# main.net
KiCad netlist of a schematic drawn in EAGLE
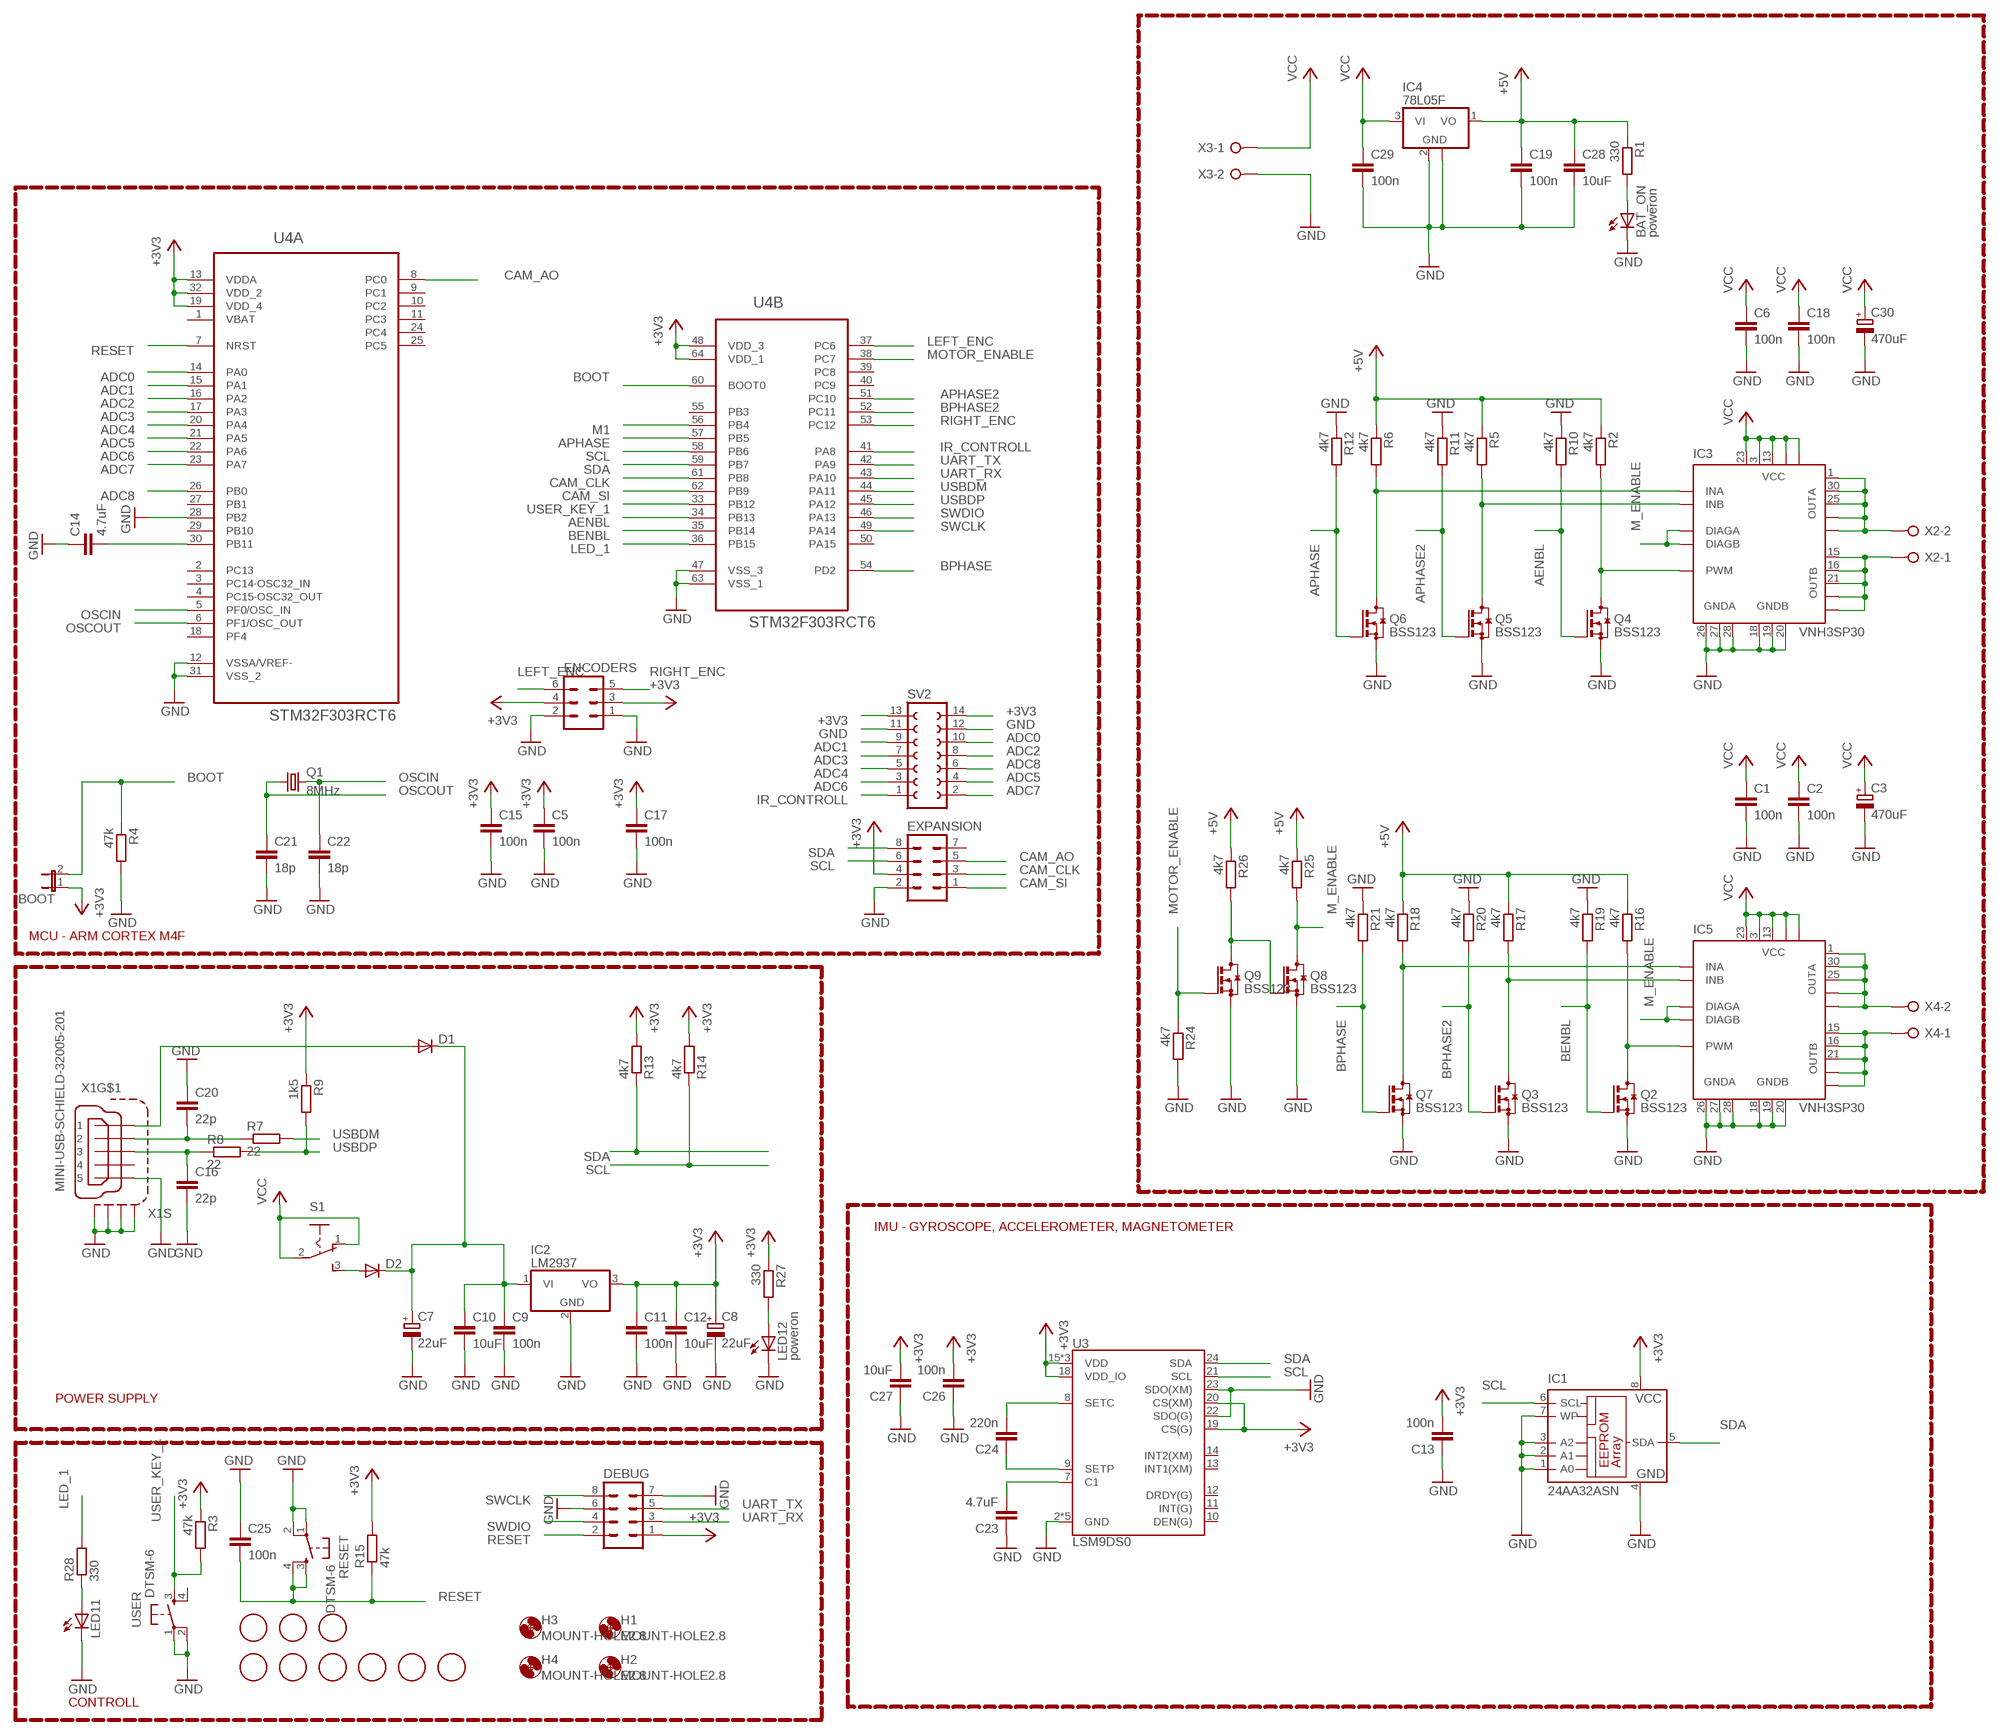
[diagram p0: schematic, sheet 1]

(export (version "E")
  (design (tool "Eeschema 10.0.6"))
  (components
    (comp (ref "BAT_ON")
      (value "poweron")
      (footprint "eagle-import:CHIPLED_1206")
      (libsource (lib "eagle-import") (part "LEDCHIPLED_1206"))
    )
    (comp (ref "BOOT")
      (value "JP1E")
      (footprint "eagle-import:JP1")
      (libsource (lib "eagle-import") (part "JP1E"))
    )
    (comp (ref "C1")
      (value "100n")
      (footprint "eagle-import:C0805")
      (libsource (lib "eagle-import") (part "C-EUC0805"))
    )
    (comp (ref "C2")
      (value "100n")
      (footprint "eagle-import:C0805")
      (libsource (lib "eagle-import") (part "C-EUC0805"))
    )
    (comp (ref "C3")
      (value "470uF")
      (footprint "eagle-import:140CLH-1014")
      (libsource (lib "eagle-import") (part "CPOL-EU140CLH-1014"))
    )
    (comp (ref "C5")
      (value "100n")
      (footprint "eagle-import:C0805")
      (libsource (lib "eagle-import") (part "C-EUC0805"))
    )
    (comp (ref "C6")
      (value "100n")
      (footprint "eagle-import:C0805")
      (libsource (lib "eagle-import") (part "C-EUC0805"))
    )
    (comp (ref "C7")
      (value "22uF")
      (footprint "eagle-import:153CLV-0505")
      (libsource (lib "eagle-import") (part "CPOL-EU153CLV-0505"))
    )
    (comp (ref "C8")
      (value "22uF")
      (footprint "eagle-import:153CLV-0505")
      (libsource (lib "eagle-import") (part "CPOL-EU153CLV-0505"))
    )
    (comp (ref "C9")
      (value "100n")
      (footprint "eagle-import:C0805")
      (libsource (lib "eagle-import") (part "C-EUC0805"))
    )
    (comp (ref "C10")
      (value "10uF")
      (footprint "eagle-import:C0805")
      (libsource (lib "eagle-import") (part "C-EUC0805"))
    )
    (comp (ref "C11")
      (value "100n")
      (footprint "eagle-import:C0805")
      (libsource (lib "eagle-import") (part "C-EUC0805"))
    )
    (comp (ref "C12")
      (value "10uF")
      (footprint "eagle-import:C0805")
      (libsource (lib "eagle-import") (part "C-EUC0805"))
    )
    (comp (ref "C13")
      (value "100n")
      (footprint "eagle-import:C0805")
      (libsource (lib "eagle-import") (part "C-EUC0805"))
    )
    (comp (ref "C14")
      (value "4.7uF")
      (footprint "eagle-import:C0805")
      (libsource (lib "eagle-import") (part "C-EUC0805"))
    )
    (comp (ref "C15")
      (value "100n")
      (footprint "eagle-import:C0805")
      (libsource (lib "eagle-import") (part "C-EUC0805"))
    )
    (comp (ref "C16")
      (value "22p")
      (footprint "eagle-import:C0805")
      (libsource (lib "eagle-import") (part "C-EUC0805"))
    )
    (comp (ref "C17")
      (value "100n")
      (footprint "eagle-import:C0805")
      (libsource (lib "eagle-import") (part "C-EUC0805"))
    )
    (comp (ref "C18")
      (value "100n")
      (footprint "eagle-import:C0805")
      (libsource (lib "eagle-import") (part "C-EUC0805"))
    )
    (comp (ref "C19")
      (value "100n")
      (footprint "eagle-import:C0805")
      (libsource (lib "eagle-import") (part "C-EUC0805"))
    )
    (comp (ref "C20")
      (value "22p")
      (footprint "eagle-import:C0805")
      (libsource (lib "eagle-import") (part "C-EUC0805"))
    )
    (comp (ref "C21")
      (value "18p")
      (footprint "eagle-import:C0805")
      (libsource (lib "eagle-import") (part "C-EUC0805"))
    )
    (comp (ref "C22")
      (value "18p")
      (footprint "eagle-import:C0805")
      (libsource (lib "eagle-import") (part "C-EUC0805"))
    )
    (comp (ref "C23")
      (value "4.7uF")
      (footprint "eagle-import:C0805")
      (libsource (lib "eagle-import") (part "C-EUC0805"))
    )
    (comp (ref "C24")
      (value "220n")
      (footprint "eagle-import:C0805")
      (libsource (lib "eagle-import") (part "C-EUC0805"))
    )
    (comp (ref "C25")
      (value "100n")
      (footprint "eagle-import:C0805")
      (libsource (lib "eagle-import") (part "C-EUC0805"))
    )
    (comp (ref "C26")
      (value "100n")
      (footprint "eagle-import:C0805")
      (libsource (lib "eagle-import") (part "C-EUC0805"))
    )
    (comp (ref "C27")
      (value "10uF")
      (footprint "eagle-import:C0805")
      (libsource (lib "eagle-import") (part "C-EUC0805"))
    )
    (comp (ref "C28")
      (value "10uF")
      (footprint "eagle-import:C0805")
      (libsource (lib "eagle-import") (part "C-EUC0805"))
    )
    (comp (ref "C29")
      (value "100n")
      (footprint "eagle-import:C0805")
      (libsource (lib "eagle-import") (part "C-EUC0805"))
    )
    (comp (ref "C30")
      (value "470uF")
      (footprint "eagle-import:140CLH-1014")
      (libsource (lib "eagle-import") (part "CPOL-EU140CLH-1014"))
    )
    (comp (ref "D1")
      (value "DIODE-SMB")
      (footprint "eagle-import:SMB")
      (libsource (lib "eagle-import") (part "DIODE-SMB"))
    )
    (comp (ref "D2")
      (value "DIODE-SMB")
      (footprint "eagle-import:SMB")
      (libsource (lib "eagle-import") (part "DIODE-SMB"))
    )
    (comp (ref "DEBUG")
      (value "MA04-2")
      (footprint "eagle-import:MA04-2")
      (libsource (lib "eagle-import") (part "MA04-2"))
    )
    (comp (ref "ENCODERS")
      (value "MA03-2")
      (footprint "eagle-import:MA03-2")
      (libsource (lib "eagle-import") (part "MA03-2"))
    )
    (comp (ref "EXPANSION")
      (value "MA04-2")
      (footprint "eagle-import:MA04-2")
      (libsource (lib "eagle-import") (part "MA04-2"))
    )
    (comp (ref "H1")
      (value "MOUNT-HOLE2.8")
      (footprint "eagle-import:2,8")
      (libsource (lib "eagle-import") (part "MOUNT-HOLE2.8"))
    )
    (comp (ref "H2")
      (value "MOUNT-HOLE2.8")
      (footprint "eagle-import:2,8")
      (libsource (lib "eagle-import") (part "MOUNT-HOLE2.8"))
    )
    (comp (ref "H3")
      (value "MOUNT-HOLE2.8")
      (footprint "eagle-import:2,8")
      (libsource (lib "eagle-import") (part "MOUNT-HOLE2.8"))
    )
    (comp (ref "H4")
      (value "MOUNT-HOLE2.8")
      (footprint "eagle-import:2,8")
      (libsource (lib "eagle-import") (part "MOUNT-HOLE2.8"))
    )
    (comp (ref "IC1")
      (value "24AA32ASN")
      (footprint "eagle-import:SO-08")
      (fields (field (name "MF") "MICROCHIP") (field (name "MPN") "24AA32A-I/SN"))
      (libsource (lib "eagle-import") (part "24SNAA32A"))
    )
    (comp (ref "IC2")
      (value "LM2937")
      (footprint "eagle-import:TO263-3")
      (libsource (lib "eagle-import") (part "LM2937"))
    )
    (comp (ref "IC3")
      (value "VNH3SP30")
      (footprint "eagle-import:MULTIPOWERSO-30")
      (fields (field (name "MPN") "VNH3SP30-E"))
      (libsource (lib "eagle-import") (part "VNH3SP30"))
    )
    (comp (ref "IC4")
      (value "78L05F")
      (footprint "eagle-import:SOT89")
      (libsource (lib "eagle-import") (part "78LF05"))
    )
    (comp (ref "IC5")
      (value "VNH3SP30")
      (footprint "eagle-import:MULTIPOWERSO-30")
      (fields (field (name "MPN") "VNH3SP30-E"))
      (libsource (lib "eagle-import") (part "VNH3SP30"))
    )
    (comp (ref "LED11")
      (value "LEDCHIPLED_1206")
      (footprint "eagle-import:CHIPLED_1206")
      (libsource (lib "eagle-import") (part "LEDCHIPLED_1206"))
    )
    (comp (ref "LED12")
      (value "poweron")
      (footprint "eagle-import:CHIPLED_1206")
      (libsource (lib "eagle-import") (part "LEDCHIPLED_1206"))
    )
    (comp (ref "Q1")
      (value "8MHz")
      (footprint "eagle-import:CTS406")
      (libsource (lib "eagle-import") (part "CRYSTALCTS406"))
    )
    (comp (ref "Q2")
      (value "BSS123")
      (footprint "eagle-import:SOT23")
      (libsource (lib "eagle-import") (part "BSS123"))
    )
    (comp (ref "Q3")
      (value "BSS123")
      (footprint "eagle-import:SOT23")
      (libsource (lib "eagle-import") (part "BSS123"))
    )
    (comp (ref "Q4")
      (value "BSS123")
      (footprint "eagle-import:SOT23")
      (libsource (lib "eagle-import") (part "BSS123"))
    )
    (comp (ref "Q5")
      (value "BSS123")
      (footprint "eagle-import:SOT23")
      (libsource (lib "eagle-import") (part "BSS123"))
    )
    (comp (ref "Q6")
      (value "BSS123")
      (footprint "eagle-import:SOT23")
      (libsource (lib "eagle-import") (part "BSS123"))
    )
    (comp (ref "Q7")
      (value "BSS123")
      (footprint "eagle-import:SOT23")
      (libsource (lib "eagle-import") (part "BSS123"))
    )
    (comp (ref "Q8")
      (value "BSS123")
      (footprint "eagle-import:SOT23")
      (libsource (lib "eagle-import") (part "BSS123"))
    )
    (comp (ref "Q9")
      (value "BSS123")
      (footprint "eagle-import:SOT23")
      (libsource (lib "eagle-import") (part "BSS123"))
    )
    (comp (ref "R1")
      (value "330")
      (footprint "eagle-import:M0805")
      (libsource (lib "eagle-import") (part "R-EU_M0805"))
    )
    (comp (ref "R2")
      (value "4k7")
      (footprint "eagle-import:M0805")
      (libsource (lib "eagle-import") (part "R-EU_M0805"))
    )
    (comp (ref "R3")
      (value "47k")
      (footprint "eagle-import:M0805")
      (libsource (lib "eagle-import") (part "R-EU_M0805"))
    )
    (comp (ref "R4")
      (value "47k")
      (footprint "eagle-import:M0805")
      (libsource (lib "eagle-import") (part "R-EU_M0805"))
    )
    (comp (ref "R5")
      (value "4k7")
      (footprint "eagle-import:M0805")
      (libsource (lib "eagle-import") (part "R-EU_M0805"))
    )
    (comp (ref "R6")
      (value "4k7")
      (footprint "eagle-import:M0805")
      (libsource (lib "eagle-import") (part "R-EU_M0805"))
    )
    (comp (ref "R7")
      (value "22")
      (footprint "eagle-import:M0805")
      (libsource (lib "eagle-import") (part "R-EU_M0805"))
    )
    (comp (ref "R8")
      (value "22")
      (footprint "eagle-import:M0805")
      (libsource (lib "eagle-import") (part "R-EU_M0805"))
    )
    (comp (ref "R9")
      (value "1k5")
      (footprint "eagle-import:M0805")
      (libsource (lib "eagle-import") (part "R-EU_M0805"))
    )
    (comp (ref "R10")
      (value "4k7")
      (footprint "eagle-import:M0805")
      (libsource (lib "eagle-import") (part "R-EU_M0805"))
    )
    (comp (ref "R11")
      (value "4k7")
      (footprint "eagle-import:M0805")
      (libsource (lib "eagle-import") (part "R-EU_M0805"))
    )
    (comp (ref "R12")
      (value "4k7")
      (footprint "eagle-import:M0805")
      (libsource (lib "eagle-import") (part "R-EU_M0805"))
    )
    (comp (ref "R13")
      (value "4k7")
      (footprint "eagle-import:M0805")
      (libsource (lib "eagle-import") (part "R-EU_M0805"))
    )
    (comp (ref "R14")
      (value "4k7")
      (footprint "eagle-import:M0805")
      (libsource (lib "eagle-import") (part "R-EU_M0805"))
    )
    (comp (ref "R15")
      (value "47k")
      (footprint "eagle-import:M0805")
      (libsource (lib "eagle-import") (part "R-EU_M0805"))
    )
    (comp (ref "R16")
      (value "4k7")
      (footprint "eagle-import:M0805")
      (libsource (lib "eagle-import") (part "R-EU_M0805"))
    )
    (comp (ref "R17")
      (value "4k7")
      (footprint "eagle-import:M0805")
      (libsource (lib "eagle-import") (part "R-EU_M0805"))
    )
    (comp (ref "R18")
      (value "4k7")
      (footprint "eagle-import:M0805")
      (libsource (lib "eagle-import") (part "R-EU_M0805"))
    )
    (comp (ref "R19")
      (value "4k7")
      (footprint "eagle-import:M0805")
      (libsource (lib "eagle-import") (part "R-EU_M0805"))
    )
    (comp (ref "R20")
      (value "4k7")
      (footprint "eagle-import:M0805")
      (libsource (lib "eagle-import") (part "R-EU_M0805"))
    )
    (comp (ref "R21")
      (value "4k7")
      (footprint "eagle-import:M0805")
      (libsource (lib "eagle-import") (part "R-EU_M0805"))
    )
    (comp (ref "R24")
      (value "4k7")
      (footprint "eagle-import:M0805")
      (libsource (lib "eagle-import") (part "R-EU_M0805"))
    )
    (comp (ref "R25")
      (value "4k7")
      (footprint "eagle-import:M0805")
      (libsource (lib "eagle-import") (part "R-EU_M0805"))
    )
    (comp (ref "R26")
      (value "4k7")
      (footprint "eagle-import:M0805")
      (libsource (lib "eagle-import") (part "R-EU_M0805"))
    )
    (comp (ref "R27")
      (value "330")
      (footprint "eagle-import:M0805")
      (libsource (lib "eagle-import") (part "R-EU_M0805"))
    )
    (comp (ref "R28")
      (value "330")
      (footprint "eagle-import:M0805")
      (libsource (lib "eagle-import") (part "R-EU_M0805"))
    )
    (comp (ref "RESET")
      (value "DTSM-6")
      (footprint "eagle-import:DTSM-6")
      (libsource (lib "eagle-import") (part "DTSM-6"))
    )
    (comp (ref "S1")
      (value "255SB")
      (footprint "eagle-import:255SB")
      (libsource (lib "eagle-import") (part "255SB"))
    )
    (comp (ref "SV2")
      (value "FE07-2")
      (footprint "eagle-import:FE07-2")
      (libsource (lib "eagle-import") (part "FE07-2"))
    )
    (comp (ref "U$1")
      (value "FIDUCIAL")
      (footprint "eagle-import:FIDUCIAL_1MM")
      (libsource (lib "eagle-import") (part "FIDUCIAL"))
    )
    (comp (ref "U$2")
      (value "FIDUCIAL")
      (footprint "eagle-import:FIDUCIAL_1MM")
      (libsource (lib "eagle-import") (part "FIDUCIAL"))
    )
    (comp (ref "U$3")
      (value "FIDUCIAL")
      (footprint "eagle-import:FIDUCIAL_1MM")
      (libsource (lib "eagle-import") (part "FIDUCIAL"))
    )
    (comp (ref "U$4")
      (value "FIDUCIAL")
      (footprint "eagle-import:FIDUCIAL_1MM")
      (libsource (lib "eagle-import") (part "FIDUCIAL"))
    )
    (comp (ref "U$5")
      (value "FIDUCIAL")
      (footprint "eagle-import:FIDUCIAL_1MM")
      (libsource (lib "eagle-import") (part "FIDUCIAL"))
    )
    (comp (ref "U$6")
      (value "FIDUCIAL")
      (footprint "eagle-import:FIDUCIAL_1MM")
      (libsource (lib "eagle-import") (part "FIDUCIAL"))
    )
    (comp (ref "U$7")
      (value "FIDUCIAL")
      (footprint "eagle-import:FIDUCIAL_1MM")
      (libsource (lib "eagle-import") (part "FIDUCIAL"))
    )
    (comp (ref "U$8")
      (value "FIDUCIAL")
      (footprint "eagle-import:FIDUCIAL_1MM")
      (libsource (lib "eagle-import") (part "FIDUCIAL"))
    )
    (comp (ref "U$9")
      (value "FIDUCIAL")
      (footprint "eagle-import:FIDUCIAL_1MM")
      (libsource (lib "eagle-import") (part "FIDUCIAL"))
    )
    (comp (ref "U3")
      (value "LSM9DS0")
      (footprint "eagle-import:LGA-24")
      (libsource (lib "eagle-import") (part "LSM9DS0"))
    )
    (comp (ref "U4")
      (value "STM32F303RCT6")
      (footprint "eagle-import:QFP50P1200X1200X160-64N")
      (libsource (lib "eagle-import") (part "STM32F303RCT6"))
    )
    (comp (ref "USER")
      (value "DTSM-6")
      (footprint "eagle-import:DTSM-6")
      (libsource (lib "eagle-import") (part "DTSM-6"))
    )
    (comp (ref "X1")
      (value "MINI-USB-SCHIELD-32005-201")
      (footprint "eagle-import:32005-201")
      (libsource (lib "eagle-import") (part "MINI-USB-SCHIELD-32005-201"))
    )
    (comp (ref "X2")
      (value "W237-02P")
      (footprint "eagle-import:W237-132")
      (libsource (lib "eagle-import") (part "W237-02P"))
    )
    (comp (ref "X3")
      (value "W237-02P")
      (footprint "eagle-import:W237-132")
      (libsource (lib "eagle-import") (part "W237-02P"))
    )
    (comp (ref "X4")
      (value "W237-02P")
      (footprint "eagle-import:W237-132")
      (libsource (lib "eagle-import") (part "W237-02P"))
    )
  )
  (nets
    (net (code "1") (name "+3V3") (class "Default")
      (node (ref "BOOT") (pin "1") (pinfunction "1_1") (pintype "passive"))
      (node (ref "C11") (pin "1") (pinfunction "1_1") (pintype "passive"))
      (node (ref "C12") (pin "1") (pinfunction "1_1") (pintype "passive"))
      (node (ref "C13") (pin "2") (pinfunction "2_2") (pintype "passive"))
      (node (ref "C15") (pin "1") (pinfunction "1_1") (pintype "passive"))
      (node (ref "C17") (pin "1") (pinfunction "1_1") (pintype "passive"))
      (node (ref "C26") (pin "2") (pinfunction "2_2") (pintype "passive"))
      (node (ref "C27") (pin "2") (pinfunction "2_2") (pintype "passive"))
      (node (ref "C5") (pin "1") (pinfunction "1_1") (pintype "passive"))
      (node (ref "C8") (pin "+") (pinfunction "+_+") (pintype "passive"))
      (node (ref "DEBUG") (pin "1") (pinfunction "1_1") (pintype "passive"))
      (node (ref "ENCODERS") (pin "3") (pinfunction "3_3") (pintype "passive"))
      (node (ref "ENCODERS") (pin "4") (pinfunction "4_4") (pintype "passive"))
      (node (ref "EXPANSION") (pin "4") (pinfunction "4_4") (pintype "passive"))
      (node (ref "IC1") (pin "8") (pinfunction "VCC_8") (pintype "power_in"))
      (node (ref "IC2") (pin "3") (pinfunction "VO_3") (pintype "passive"))
      (node (ref "R13") (pin "2") (pinfunction "2_2") (pintype "passive"))
      (node (ref "R14") (pin "2") (pinfunction "2_2") (pintype "passive"))
      (node (ref "R15") (pin "2") (pinfunction "2_2") (pintype "passive"))
      (node (ref "R27") (pin "1") (pinfunction "1_1") (pintype "passive"))
      (node (ref "R3") (pin "1") (pinfunction "1_1") (pintype "passive"))
      (node (ref "R9") (pin "1") (pinfunction "1_1") (pintype "passive"))
      (node (ref "SV2") (pin "13") (pinfunction "13_13") (pintype "passive"))
      (node (ref "SV2") (pin "14") (pinfunction "14_14") (pintype "passive"))
      (node (ref "U3") (pin "15") (pinfunction "VDD_15") (pintype "bidirectional"))
      (node (ref "U3") (pin "16") (pinfunction "VDD_16") (pintype "bidirectional"))
      (node (ref "U3") (pin "17") (pinfunction "VDD_17") (pintype "bidirectional"))
      (node (ref "U3") (pin "18") (pinfunction "VDD_IO_18") (pintype "bidirectional"))
      (node (ref "U3") (pin "19") (pinfunction "CS(G)_19") (pintype "bidirectional"))
      (node (ref "U3") (pin "20") (pinfunction "CS(XM)_20") (pintype "bidirectional"))
      (node (ref "U4") (pin "13") (pinfunction "VDDA_13") (pintype "power_in"))
      (node (ref "U4") (pin "19") (pinfunction "VDD_4_19") (pintype "power_in"))
      (node (ref "U4") (pin "32") (pinfunction "VDD_2_32") (pintype "power_in"))
      (node (ref "U4") (pin "48") (pinfunction "VDD_3_48") (pintype "power_in"))
      (node (ref "U4") (pin "64") (pinfunction "VDD_1_64") (pintype "power_in"))
    )
    (net (code "2") (name "+5V") (class "Default")
      (node (ref "C19") (pin "1") (pinfunction "1_1") (pintype "passive"))
      (node (ref "C28") (pin "1") (pinfunction "1_1") (pintype "passive"))
      (node (ref "IC4") (pin "1") (pinfunction "VO_1") (pintype "passive"))
      (node (ref "R1") (pin "1") (pinfunction "1_1") (pintype "passive"))
      (node (ref "R16") (pin "1") (pinfunction "1_1") (pintype "passive"))
      (node (ref "R17") (pin "1") (pinfunction "1_1") (pintype "passive"))
      (node (ref "R18") (pin "1") (pinfunction "1_1") (pintype "passive"))
      (node (ref "R2") (pin "1") (pinfunction "1_1") (pintype "passive"))
      (node (ref "R25") (pin "1") (pinfunction "1_1") (pintype "passive"))
      (node (ref "R26") (pin "1") (pinfunction "1_1") (pintype "passive"))
      (node (ref "R5") (pin "1") (pinfunction "1_1") (pintype "passive"))
      (node (ref "R6") (pin "1") (pinfunction "1_1") (pintype "passive"))
    )
    (net (code "3") (name "/ADC0") (class "Default")
      (node (ref "SV2") (pin "10") (pinfunction "10_10") (pintype "passive"))
      (node (ref "U4") (pin "14") (pinfunction "PA0_14") (pintype "bidirectional"))
    )
    (net (code "4") (name "/ADC1") (class "Default")
      (node (ref "SV2") (pin "9") (pinfunction "9_9") (pintype "passive"))
      (node (ref "U4") (pin "15") (pinfunction "PA1_15") (pintype "bidirectional"))
    )
    (net (code "5") (name "/ADC2") (class "Default")
      (node (ref "SV2") (pin "8") (pinfunction "8_8") (pintype "passive"))
      (node (ref "U4") (pin "16") (pinfunction "PA2_16") (pintype "bidirectional"))
    )
    (net (code "6") (name "/ADC3") (class "Default")
      (node (ref "SV2") (pin "7") (pinfunction "7_7") (pintype "passive"))
      (node (ref "U4") (pin "17") (pinfunction "PA3_17") (pintype "bidirectional"))
    )
    (net (code "7") (name "/ADC4") (class "Default")
      (node (ref "SV2") (pin "5") (pinfunction "5_5") (pintype "passive"))
      (node (ref "U4") (pin "20") (pinfunction "PA4_20") (pintype "bidirectional"))
    )
    (net (code "8") (name "/ADC5") (class "Default")
      (node (ref "SV2") (pin "4") (pinfunction "4_4") (pintype "passive"))
      (node (ref "U4") (pin "21") (pinfunction "PA5_21") (pintype "bidirectional"))
    )
    (net (code "9") (name "/ADC6") (class "Default")
      (node (ref "SV2") (pin "3") (pinfunction "3_3") (pintype "passive"))
      (node (ref "U4") (pin "22") (pinfunction "PA6_22") (pintype "bidirectional"))
    )
    (net (code "10") (name "/ADC7") (class "Default")
      (node (ref "SV2") (pin "2") (pinfunction "2_2") (pintype "passive"))
      (node (ref "U4") (pin "23") (pinfunction "PA7_23") (pintype "bidirectional"))
    )
    (net (code "11") (name "/ADC8") (class "Default")
      (node (ref "SV2") (pin "6") (pinfunction "6_6") (pintype "passive"))
      (node (ref "U4") (pin "26") (pinfunction "PB0_26") (pintype "bidirectional"))
    )
    (net (code "12") (name "/AENBL") (class "Default")
      (node (ref "Q4") (pin "1") (pinfunction "G_1") (pintype "passive"))
      (node (ref "R10") (pin "2") (pinfunction "2_2") (pintype "passive"))
      (node (ref "U4") (pin "34") (pinfunction "PB13_34") (pintype "bidirectional"))
    )
    (net (code "13") (name "/APHASE") (class "Default")
      (node (ref "Q6") (pin "1") (pinfunction "G_1") (pintype "passive"))
      (node (ref "R12") (pin "2") (pinfunction "2_2") (pintype "passive"))
      (node (ref "U4") (pin "57") (pinfunction "PB5_57") (pintype "bidirectional"))
    )
    (net (code "14") (name "/APHASE2") (class "Default")
      (node (ref "Q5") (pin "1") (pinfunction "G_1") (pintype "passive"))
      (node (ref "R11") (pin "2") (pinfunction "2_2") (pintype "passive"))
      (node (ref "U4") (pin "51") (pinfunction "PC10_51") (pintype "bidirectional"))
    )
    (net (code "15") (name "/BENBL") (class "Default")
      (node (ref "Q2") (pin "1") (pinfunction "G_1") (pintype "passive"))
      (node (ref "R19") (pin "2") (pinfunction "2_2") (pintype "passive"))
      (node (ref "U4") (pin "35") (pinfunction "PB14_35") (pintype "bidirectional"))
    )
    (net (code "16") (name "/BOOT") (class "Default")
      (node (ref "BOOT") (pin "2") (pinfunction "2_2") (pintype "passive"))
      (node (ref "R4") (pin "1") (pinfunction "1_1") (pintype "passive"))
      (node (ref "U4") (pin "60") (pinfunction "BOOT0_60") (pintype "input"))
    )
    (net (code "17") (name "/BPHASE") (class "Default")
      (node (ref "Q7") (pin "1") (pinfunction "G_1") (pintype "passive"))
      (node (ref "R21") (pin "2") (pinfunction "2_2") (pintype "passive"))
      (node (ref "U4") (pin "54") (pinfunction "PD2_54") (pintype "bidirectional"))
    )
    (net (code "18") (name "/BPHASE2") (class "Default")
      (node (ref "Q3") (pin "1") (pinfunction "G_1") (pintype "passive"))
      (node (ref "R20") (pin "2") (pinfunction "2_2") (pintype "passive"))
      (node (ref "U4") (pin "52") (pinfunction "PC11_52") (pintype "bidirectional"))
    )
    (net (code "19") (name "/CAM_AO") (class "Default")
      (node (ref "EXPANSION") (pin "5") (pinfunction "5_5") (pintype "passive"))
      (node (ref "U4") (pin "8") (pinfunction "PC0_8") (pintype "bidirectional"))
    )
    (net (code "20") (name "/CAM_CLK") (class "Default")
      (node (ref "EXPANSION") (pin "3") (pinfunction "3_3") (pintype "passive"))
      (node (ref "U4") (pin "61") (pinfunction "PB8_61") (pintype "bidirectional"))
    )
    (net (code "21") (name "/CAM_SI") (class "Default")
      (node (ref "EXPANSION") (pin "1") (pinfunction "1_1") (pintype "passive"))
      (node (ref "U4") (pin "62") (pinfunction "PB9_62") (pintype "bidirectional"))
    )
    (net (code "22") (name "/IR_CONTROLL") (class "Default")
      (node (ref "SV2") (pin "1") (pinfunction "1_1") (pintype "passive"))
      (node (ref "U4") (pin "41") (pinfunction "PA8_41") (pintype "bidirectional"))
    )
    (net (code "23") (name "/LED_1") (class "Default")
      (node (ref "R28") (pin "2") (pinfunction "2_2") (pintype "passive"))
      (node (ref "U4") (pin "36") (pinfunction "PB15_36") (pintype "bidirectional"))
    )
    (net (code "24") (name "/LEFT_ENC") (class "Default")
      (node (ref "ENCODERS") (pin "6") (pinfunction "6_6") (pintype "passive"))
      (node (ref "U4") (pin "37") (pinfunction "PC6_37") (pintype "bidirectional"))
    )
    (net (code "25") (name "/M1") (class "Default")
      (node (ref "U4") (pin "56") (pinfunction "PB4_56") (pintype "bidirectional"))
    )
    (net (code "26") (name "/MOTOR_ENABLE") (class "Default")
      (node (ref "Q9") (pin "1") (pinfunction "G_1") (pintype "passive"))
      (node (ref "R24") (pin "1") (pinfunction "1_1") (pintype "passive"))
      (node (ref "U4") (pin "38") (pinfunction "PC7_38") (pintype "bidirectional"))
    )
    (net (code "27") (name "/M_ENABLE") (class "Default")
      (node (ref "IC3") (pin "10") (pinfunction "DIAGB_10") (pintype "open_collector"))
      (node (ref "IC3") (pin "6") (pinfunction "DIAGA_6") (pintype "open_collector"))
      (node (ref "IC5") (pin "10") (pinfunction "DIAGB_10") (pintype "open_collector"))
      (node (ref "IC5") (pin "6") (pinfunction "DIAGA_6") (pintype "open_collector"))
      (node (ref "Q8") (pin "3") (pinfunction "D_3") (pintype "passive"))
      (node (ref "R25") (pin "2") (pinfunction "2_2") (pintype "passive"))
    )
    (net (code "28") (name "/OSCIN") (class "Default")
      (node (ref "C22") (pin "1") (pinfunction "1_1") (pintype "passive"))
      (node (ref "Q1") (pin "3") (pinfunction "2_3") (pintype "passive"))
      (node (ref "U4") (pin "5") (pinfunction "PF0/OSC_IN_5") (pintype "bidirectional"))
    )
    (net (code "29") (name "/OSCOUT") (class "Default")
      (node (ref "C21") (pin "1") (pinfunction "1_1") (pintype "passive"))
      (node (ref "Q1") (pin "1") (pinfunction "1_1") (pintype "passive"))
      (node (ref "U4") (pin "6") (pinfunction "PF1/OSC_OUT_6") (pintype "bidirectional"))
    )
    (net (code "30") (name "/RESET") (class "Default")
      (node (ref "C25") (pin "2") (pinfunction "2_2") (pintype "passive"))
      (node (ref "DEBUG") (pin "2") (pinfunction "2_2") (pintype "passive"))
      (node (ref "R15") (pin "1") (pinfunction "1_1") (pintype "passive"))
      (node (ref "RESET") (pin "3") (pinfunction "3_3") (pintype "passive"))
      (node (ref "RESET") (pin "4") (pinfunction "4_4") (pintype "passive"))
      (node (ref "U4") (pin "7") (pinfunction "NRST_7") (pintype "bidirectional"))
    )
    (net (code "31") (name "/RIGHT_ENC") (class "Default")
      (node (ref "ENCODERS") (pin "5") (pinfunction "5_5") (pintype "passive"))
      (node (ref "U4") (pin "53") (pinfunction "PC12_53") (pintype "bidirectional"))
    )
    (net (code "32") (name "/SCL") (class "Default")
      (node (ref "EXPANSION") (pin "6") (pinfunction "6_6") (pintype "passive"))
      (node (ref "IC1") (pin "6") (pinfunction "SCL_6") (pintype "input"))
      (node (ref "R14") (pin "1") (pinfunction "1_1") (pintype "passive"))
      (node (ref "U3") (pin "21") (pinfunction "SCL_21") (pintype "bidirectional"))
      (node (ref "U4") (pin "58") (pinfunction "PB6_58") (pintype "bidirectional"))
    )
    (net (code "33") (name "/SDA") (class "Default")
      (node (ref "EXPANSION") (pin "8") (pinfunction "8_8") (pintype "passive"))
      (node (ref "IC1") (pin "5") (pinfunction "SDA_5") (pintype "bidirectional"))
      (node (ref "R13") (pin "1") (pinfunction "1_1") (pintype "passive"))
      (node (ref "U3") (pin "24") (pinfunction "SDA_24") (pintype "bidirectional"))
      (node (ref "U4") (pin "59") (pinfunction "PB7_59") (pintype "bidirectional"))
    )
    (net (code "34") (name "/SWCLK") (class "Default")
      (node (ref "DEBUG") (pin "8") (pinfunction "8_8") (pintype "passive"))
      (node (ref "U4") (pin "49") (pinfunction "PA14_49") (pintype "bidirectional"))
    )
    (net (code "35") (name "/SWDIO") (class "Default")
      (node (ref "DEBUG") (pin "4") (pinfunction "4_4") (pintype "passive"))
      (node (ref "U4") (pin "46") (pinfunction "PA13_46") (pintype "bidirectional"))
    )
    (net (code "36") (name "/UART_RX") (class "Default")
      (node (ref "DEBUG") (pin "3") (pinfunction "3_3") (pintype "passive"))
      (node (ref "U4") (pin "43") (pinfunction "PA10_43") (pintype "bidirectional"))
    )
    (net (code "37") (name "/UART_TX") (class "Default")
      (node (ref "DEBUG") (pin "5") (pinfunction "5_5") (pintype "passive"))
      (node (ref "U4") (pin "42") (pinfunction "PA9_42") (pintype "bidirectional"))
    )
    (net (code "38") (name "/USBDM") (class "Default")
      (node (ref "R7") (pin "2") (pinfunction "2_2") (pintype "passive"))
      (node (ref "U4") (pin "44") (pinfunction "PA11_44") (pintype "bidirectional"))
    )
    (net (code "39") (name "/USBDP") (class "Default")
      (node (ref "R8") (pin "2") (pinfunction "2_2") (pintype "passive"))
      (node (ref "R9") (pin "2") (pinfunction "2_2") (pintype "passive"))
      (node (ref "U4") (pin "45") (pinfunction "PA12_45") (pintype "bidirectional"))
    )
    (net (code "40") (name "/USER_KEY_1") (class "Default")
      (node (ref "R3") (pin "2") (pinfunction "2_2") (pintype "passive"))
      (node (ref "U4") (pin "33") (pinfunction "PB12_33") (pintype "bidirectional"))
      (node (ref "USER") (pin "3") (pinfunction "3_3") (pintype "passive"))
    )
    (net (code "41") (name "/VBAT") (class "Default")
      (node (ref "U4") (pin "1") (pinfunction "VBAT_1") (pintype "power_in"))
    )
    (net (code "42") (name "GND") (class "Default")
      (node (ref "BAT_ON") (pin "C") (pinfunction "C_C") (pintype "passive"))
      (node (ref "C1") (pin "2") (pinfunction "2_2") (pintype "passive"))
      (node (ref "C10") (pin "2") (pinfunction "2_2") (pintype "passive"))
      (node (ref "C11") (pin "2") (pinfunction "2_2") (pintype "passive"))
      (node (ref "C12") (pin "2") (pinfunction "2_2") (pintype "passive"))
      (node (ref "C13") (pin "1") (pinfunction "1_1") (pintype "passive"))
      (node (ref "C14") (pin "1") (pinfunction "1_1") (pintype "passive"))
      (node (ref "C15") (pin "2") (pinfunction "2_2") (pintype "passive"))
      (node (ref "C16") (pin "2") (pinfunction "2_2") (pintype "passive"))
      (node (ref "C17") (pin "2") (pinfunction "2_2") (pintype "passive"))
      (node (ref "C18") (pin "2") (pinfunction "2_2") (pintype "passive"))
      (node (ref "C19") (pin "2") (pinfunction "2_2") (pintype "passive"))
      (node (ref "C2") (pin "2") (pinfunction "2_2") (pintype "passive"))
      (node (ref "C20") (pin "1") (pinfunction "1_1") (pintype "passive"))
      (node (ref "C21") (pin "2") (pinfunction "2_2") (pintype "passive"))
      (node (ref "C22") (pin "2") (pinfunction "2_2") (pintype "passive"))
      (node (ref "C23") (pin "1") (pinfunction "1_1") (pintype "passive"))
      (node (ref "C25") (pin "1") (pinfunction "1_1") (pintype "passive"))
      (node (ref "C26") (pin "1") (pinfunction "1_1") (pintype "passive"))
      (node (ref "C27") (pin "1") (pinfunction "1_1") (pintype "passive"))
      (node (ref "C28") (pin "2") (pinfunction "2_2") (pintype "passive"))
      (node (ref "C29") (pin "2") (pinfunction "2_2") (pintype "passive"))
      (node (ref "C3") (pin "-") (pinfunction "-_-") (pintype "passive"))
      (node (ref "C30") (pin "-") (pinfunction "-_-") (pintype "passive"))
      (node (ref "C5") (pin "2") (pinfunction "2_2") (pintype "passive"))
      (node (ref "C6") (pin "2") (pinfunction "2_2") (pintype "passive"))
      (node (ref "C7") (pin "-") (pinfunction "-_-") (pintype "passive"))
      (node (ref "C8") (pin "-") (pinfunction "-_-") (pintype "passive"))
      (node (ref "C9") (pin "2") (pinfunction "2_2") (pintype "passive"))
      (node (ref "DEBUG") (pin "6") (pinfunction "6_6") (pintype "passive"))
      (node (ref "DEBUG") (pin "7") (pinfunction "7_7") (pintype "passive"))
      (node (ref "ENCODERS") (pin "1") (pinfunction "1_1") (pintype "passive"))
      (node (ref "ENCODERS") (pin "2") (pinfunction "2_2") (pintype "passive"))
      (node (ref "EXPANSION") (pin "2") (pinfunction "2_2") (pintype "passive"))
      (node (ref "IC1") (pin "1") (pinfunction "A0_1") (pintype "input"))
      (node (ref "IC1") (pin "2") (pinfunction "A1_2") (pintype "input"))
      (node (ref "IC1") (pin "3") (pinfunction "A2_3") (pintype "input"))
      (node (ref "IC1") (pin "4") (pinfunction "GND_4") (pintype "power_in"))
      (node (ref "IC1") (pin "7") (pinfunction "WP_7") (pintype "input"))
      (node (ref "IC2") (pin "2") (pinfunction "GND_2") (pintype "passive"))
      (node (ref "IC3") (pin "18") (pinfunction "GNDB_18") (pintype "power_in"))
      (node (ref "IC3") (pin "19") (pinfunction "GNDB_19") (pintype "power_in"))
      (node (ref "IC3") (pin "20") (pinfunction "GNDB_20") (pintype "power_in"))
      (node (ref "IC3") (pin "26") (pinfunction "GNDA_26") (pintype "power_in"))
      (node (ref "IC3") (pin "27") (pinfunction "GNDA_27") (pintype "power_in"))
      (node (ref "IC3") (pin "28") (pinfunction "GNDA_28") (pintype "power_in"))
      (node (ref "IC4") (pin "2") (pinfunction "GND_2") (pintype "passive"))
      (node (ref "IC4") (pin "2@1") (pinfunction "GND_2@1") (pintype "passive"))
      (node (ref "IC5") (pin "18") (pinfunction "GNDB_18") (pintype "power_in"))
      (node (ref "IC5") (pin "19") (pinfunction "GNDB_19") (pintype "power_in"))
      (node (ref "IC5") (pin "20") (pinfunction "GNDB_20") (pintype "power_in"))
      (node (ref "IC5") (pin "26") (pinfunction "GNDA_26") (pintype "power_in"))
      (node (ref "IC5") (pin "27") (pinfunction "GNDA_27") (pintype "power_in"))
      (node (ref "IC5") (pin "28") (pinfunction "GNDA_28") (pintype "power_in"))
      (node (ref "LED11") (pin "C") (pinfunction "C_C") (pintype "passive"))
      (node (ref "LED12") (pin "C") (pinfunction "C_C") (pintype "passive"))
      (node (ref "Q2") (pin "2") (pinfunction "S_2") (pintype "passive"))
      (node (ref "Q3") (pin "2") (pinfunction "S_2") (pintype "passive"))
      (node (ref "Q4") (pin "2") (pinfunction "S_2") (pintype "passive"))
      (node (ref "Q5") (pin "2") (pinfunction "S_2") (pintype "passive"))
      (node (ref "Q6") (pin "2") (pinfunction "S_2") (pintype "passive"))
      (node (ref "Q7") (pin "2") (pinfunction "S_2") (pintype "passive"))
      (node (ref "Q8") (pin "2") (pinfunction "S_2") (pintype "passive"))
      (node (ref "Q9") (pin "2") (pinfunction "S_2") (pintype "passive"))
      (node (ref "R10") (pin "1") (pinfunction "1_1") (pintype "passive"))
      (node (ref "R11") (pin "1") (pinfunction "1_1") (pintype "passive"))
      (node (ref "R12") (pin "1") (pinfunction "1_1") (pintype "passive"))
      (node (ref "R19") (pin "1") (pinfunction "1_1") (pintype "passive"))
      (node (ref "R20") (pin "1") (pinfunction "1_1") (pintype "passive"))
      (node (ref "R21") (pin "1") (pinfunction "1_1") (pintype "passive"))
      (node (ref "R24") (pin "2") (pinfunction "2_2") (pintype "passive"))
      (node (ref "R4") (pin "2") (pinfunction "2_2") (pintype "passive"))
      (node (ref "RESET") (pin "1") (pinfunction "1_1") (pintype "passive"))
      (node (ref "RESET") (pin "2") (pinfunction "2_2") (pintype "passive"))
      (node (ref "SV2") (pin "11") (pinfunction "11_11") (pintype "passive"))
      (node (ref "SV2") (pin "12") (pinfunction "12_12") (pintype "passive"))
      (node (ref "U3") (pin "2") (pinfunction "GND_2") (pintype "bidirectional"))
      (node (ref "U3") (pin "22") (pinfunction "SDO(G)_22") (pintype "bidirectional"))
      (node (ref "U3") (pin "23") (pinfunction "SDO(XM)_23") (pintype "bidirectional"))
      (node (ref "U3") (pin "3") (pinfunction "GND_3") (pintype "bidirectional"))
      (node (ref "U3") (pin "4") (pinfunction "GND_4") (pintype "bidirectional"))
      (node (ref "U3") (pin "5") (pinfunction "GND_5") (pintype "bidirectional"))
      (node (ref "U3") (pin "6") (pinfunction "GND_6") (pintype "bidirectional"))
      (node (ref "U4") (pin "12") (pinfunction "VSSA/VREF-_12") (pintype "power_in"))
      (node (ref "U4") (pin "28") (pinfunction "PB2_28") (pintype "bidirectional"))
      (node (ref "U4") (pin "31") (pinfunction "VSS_2_31") (pintype "passive"))
      (node (ref "U4") (pin "47") (pinfunction "VSS_3_47") (pintype "passive"))
      (node (ref "U4") (pin "63") (pinfunction "VSS_1_63") (pintype "passive"))
      (node (ref "USER") (pin "1") (pinfunction "1_1") (pintype "passive"))
      (node (ref "USER") (pin "2") (pinfunction "2_2") (pintype "passive"))
      (node (ref "X1") (pin "5") (pinfunction "5_5") (pintype "passive"))
      (node (ref "X1") (pin "M1") (pinfunction "S1_M1") (pintype "passive"))
      (node (ref "X1") (pin "M2") (pinfunction "S2_M2") (pintype "passive"))
      (node (ref "X1") (pin "M3") (pinfunction "S3_M3") (pintype "passive"))
      (node (ref "X1") (pin "M4") (pinfunction "S4_M4") (pintype "passive"))
      (node (ref "X3") (pin "2") (pinfunction "KL_2") (pintype "passive"))
    )
    (net (code "43") (name "Net-(BAT_ON-PadA)") (class "Default")
      (node (ref "BAT_ON") (pin "A") (pinfunction "A_A") (pintype "passive"))
      (node (ref "R1") (pin "2") (pinfunction "2_2") (pintype "passive"))
    )
    (net (code "44") (name "Net-(C16-Pad1)") (class "Default")
      (node (ref "C16") (pin "1") (pinfunction "1_1") (pintype "passive"))
      (node (ref "R8") (pin "1") (pinfunction "1_1") (pintype "passive"))
      (node (ref "X1") (pin "3") (pinfunction "3_3") (pintype "passive"))
    )
    (net (code "45") (name "Net-(C20-Pad2)") (class "Default")
      (node (ref "C20") (pin "2") (pinfunction "2_2") (pintype "passive"))
      (node (ref "R7") (pin "1") (pinfunction "1_1") (pintype "passive"))
      (node (ref "X1") (pin "2") (pinfunction "2_2") (pintype "passive"))
    )
    (net (code "46") (name "Net-(D1-PadA)") (class "Default")
      (node (ref "D1") (pin "A") (pinfunction "A_A") (pintype "passive"))
      (node (ref "X1") (pin "1") (pinfunction "1_1") (pintype "passive"))
    )
    (net (code "47") (name "Net-(IC2-VI)") (class "Default")
      (node (ref "C10") (pin "1") (pinfunction "1_1") (pintype "passive"))
      (node (ref "C7") (pin "+") (pinfunction "+_+") (pintype "passive"))
      (node (ref "C9") (pin "1") (pinfunction "1_1") (pintype "passive"))
      (node (ref "D1") (pin "C") (pinfunction "C_C") (pintype "passive"))
      (node (ref "D2") (pin "C") (pinfunction "C_C") (pintype "passive"))
      (node (ref "IC2") (pin "1") (pinfunction "VI_1") (pintype "input"))
    )
    (net (code "48") (name "Net-(IC3-INA)") (class "Default")
      (node (ref "IC3") (pin "5") (pinfunction "INA_5") (pintype "input"))
      (node (ref "Q6") (pin "3") (pinfunction "D_3") (pintype "passive"))
      (node (ref "R6") (pin "2") (pinfunction "2_2") (pintype "passive"))
    )
    (net (code "49") (name "Net-(IC3-INB)") (class "Default")
      (node (ref "IC3") (pin "11") (pinfunction "INB_11") (pintype "input"))
      (node (ref "Q5") (pin "3") (pinfunction "D_3") (pintype "passive"))
      (node (ref "R5") (pin "2") (pinfunction "2_2") (pintype "passive"))
    )
    (net (code "50") (name "Net-(IC3-PWM)") (class "Default")
      (node (ref "IC3") (pin "8") (pinfunction "PWM_8") (pintype "input"))
      (node (ref "Q4") (pin "3") (pinfunction "D_3") (pintype "passive"))
      (node (ref "R2") (pin "2") (pinfunction "2_2") (pintype "passive"))
    )
    (net (code "51") (name "Net-(IC5-INA)") (class "Default")
      (node (ref "IC5") (pin "5") (pinfunction "INA_5") (pintype "input"))
      (node (ref "Q7") (pin "3") (pinfunction "D_3") (pintype "passive"))
      (node (ref "R18") (pin "2") (pinfunction "2_2") (pintype "passive"))
    )
    (net (code "52") (name "Net-(IC5-INB)") (class "Default")
      (node (ref "IC5") (pin "11") (pinfunction "INB_11") (pintype "input"))
      (node (ref "Q3") (pin "3") (pinfunction "D_3") (pintype "passive"))
      (node (ref "R17") (pin "2") (pinfunction "2_2") (pintype "passive"))
    )
    (net (code "53") (name "Net-(IC5-PWM)") (class "Default")
      (node (ref "IC5") (pin "8") (pinfunction "PWM_8") (pintype "input"))
      (node (ref "Q2") (pin "3") (pinfunction "D_3") (pintype "passive"))
      (node (ref "R16") (pin "2") (pinfunction "2_2") (pintype "passive"))
    )
    (net (code "54") (name "Net-(LED11-PadA)") (class "Default")
      (node (ref "LED11") (pin "A") (pinfunction "A_A") (pintype "passive"))
      (node (ref "R28") (pin "1") (pinfunction "1_1") (pintype "passive"))
    )
    (net (code "55") (name "Net-(LED12-PadA)") (class "Default")
      (node (ref "LED12") (pin "A") (pinfunction "A_A") (pintype "passive"))
      (node (ref "R27") (pin "2") (pinfunction "2_2") (pintype "passive"))
    )
    (net (code "56") (name "Net-(Q8-G)") (class "Default")
      (node (ref "Q8") (pin "1") (pinfunction "G_1") (pintype "passive"))
      (node (ref "Q9") (pin "3") (pinfunction "D_3") (pintype "passive"))
      (node (ref "R26") (pin "2") (pinfunction "2_2") (pintype "passive"))
    )
    (net (code "57") (name "Net-(S1-S)") (class "Default")
      (node (ref "D2") (pin "A") (pinfunction "A_A") (pintype "passive"))
      (node (ref "S1") (pin "3") (pinfunction "S_3") (pintype "passive"))
    )
    (net (code "58") (name "Net-(U3-C1)") (class "Default")
      (node (ref "C23") (pin "2") (pinfunction "2_2") (pintype "passive"))
      (node (ref "U3") (pin "7") (pinfunction "C1_7") (pintype "bidirectional"))
    )
    (net (code "59") (name "Net-(U3-SETC)") (class "Default")
      (node (ref "C24") (pin "2") (pinfunction "2_2") (pintype "passive"))
      (node (ref "U3") (pin "8") (pinfunction "SETC_8") (pintype "bidirectional"))
    )
    (net (code "60") (name "Net-(U3-SETP)") (class "Default")
      (node (ref "C24") (pin "1") (pinfunction "1_1") (pintype "passive"))
      (node (ref "U3") (pin "9") (pinfunction "SETP_9") (pintype "bidirectional"))
    )
    (net (code "61") (name "Net-(U4A-PB11)") (class "Default")
      (node (ref "C14") (pin "2") (pinfunction "2_2") (pintype "passive"))
      (node (ref "U4") (pin "30") (pinfunction "PB11_30") (pintype "bidirectional"))
    )
    (net (code "62") (name "Net-(X2A-KL)") (class "Default")
      (node (ref "IC3") (pin "15") (pinfunction "OUTB_15") (pintype "output"))
      (node (ref "IC3") (pin "16") (pinfunction "OUTB_16") (pintype "passive"))
      (node (ref "IC3") (pin "21") (pinfunction "OUTB_21") (pintype "passive"))
      (node (ref "IC3") (pin "OUTB") (pinfunction "OUTB_OUTB") (pintype "passive"))
      (node (ref "IC3") (pin "OUTB@1") (pinfunction "OUTB_OUTB@1") (pintype "passive"))
      (node (ref "X2") (pin "1") (pinfunction "KL_1") (pintype "passive"))
    )
    (net (code "63") (name "Net-(X2B-KL)") (class "Default")
      (node (ref "IC3") (pin "1") (pinfunction "OUTA_1") (pintype "output"))
      (node (ref "IC3") (pin "25") (pinfunction "OUTA_25") (pintype "passive"))
      (node (ref "IC3") (pin "30") (pinfunction "OUTA_30") (pintype "passive"))
      (node (ref "IC3") (pin "OUTA") (pinfunction "OUTA_OUTA") (pintype "passive"))
      (node (ref "IC3") (pin "OUTA@1") (pinfunction "OUTA_OUTA@1") (pintype "passive"))
      (node (ref "X2") (pin "2") (pinfunction "KL_2") (pintype "passive"))
    )
    (net (code "64") (name "Net-(X4A-KL)") (class "Default")
      (node (ref "IC5") (pin "15") (pinfunction "OUTB_15") (pintype "output"))
      (node (ref "IC5") (pin "16") (pinfunction "OUTB_16") (pintype "passive"))
      (node (ref "IC5") (pin "21") (pinfunction "OUTB_21") (pintype "passive"))
      (node (ref "IC5") (pin "OUTB") (pinfunction "OUTB_OUTB") (pintype "passive"))
      (node (ref "IC5") (pin "OUTB@1") (pinfunction "OUTB_OUTB@1") (pintype "passive"))
      (node (ref "X4") (pin "1") (pinfunction "KL_1") (pintype "passive"))
    )
    (net (code "65") (name "Net-(X4B-KL)") (class "Default")
      (node (ref "IC5") (pin "1") (pinfunction "OUTA_1") (pintype "output"))
      (node (ref "IC5") (pin "25") (pinfunction "OUTA_25") (pintype "passive"))
      (node (ref "IC5") (pin "30") (pinfunction "OUTA_30") (pintype "passive"))
      (node (ref "IC5") (pin "OUTA") (pinfunction "OUTA_OUTA") (pintype "passive"))
      (node (ref "IC5") (pin "OUTA@1") (pinfunction "OUTA_OUTA@1") (pintype "passive"))
      (node (ref "X4") (pin "2") (pinfunction "KL_2") (pintype "passive"))
    )
    (net (code "66") (name "VCC") (class "Default")
      (node (ref "C1") (pin "1") (pinfunction "1_1") (pintype "passive"))
      (node (ref "C18") (pin "1") (pinfunction "1_1") (pintype "passive"))
      (node (ref "C2") (pin "1") (pinfunction "1_1") (pintype "passive"))
      (node (ref "C29") (pin "1") (pinfunction "1_1") (pintype "passive"))
      (node (ref "C3") (pin "+") (pinfunction "+_+") (pintype "passive"))
      (node (ref "C30") (pin "+") (pinfunction "+_+") (pintype "passive"))
      (node (ref "C6") (pin "1") (pinfunction "1_1") (pintype "passive"))
      (node (ref "IC3") (pin "13") (pinfunction "VCC_13") (pintype "power_in"))
      (node (ref "IC3") (pin "23") (pinfunction "VCC_23") (pintype "power_in"))
      (node (ref "IC3") (pin "3") (pinfunction "VCC_3") (pintype "power_in"))
      (node (ref "IC3") (pin "VCC") (pinfunction "VCC_VCC") (pintype "power_in"))
      (node (ref "IC3") (pin "VCC@1") (pinfunction "VCC_VCC@1") (pintype "power_in"))
      (node (ref "IC4") (pin "3") (pinfunction "VI_3") (pintype "input"))
      (node (ref "IC5") (pin "13") (pinfunction "VCC_13") (pintype "power_in"))
      (node (ref "IC5") (pin "23") (pinfunction "VCC_23") (pintype "power_in"))
      (node (ref "IC5") (pin "3") (pinfunction "VCC_3") (pintype "power_in"))
      (node (ref "IC5") (pin "VCC") (pinfunction "VCC_VCC") (pintype "power_in"))
      (node (ref "IC5") (pin "VCC@1") (pinfunction "VCC_VCC@1") (pintype "power_in"))
      (node (ref "S1") (pin "1") (pinfunction "O_1") (pintype "passive"))
      (node (ref "S1") (pin "2") (pinfunction "P_2") (pintype "passive"))
      (node (ref "X3") (pin "1") (pinfunction "KL_1") (pintype "passive"))
    )
    (net (code "67") (name "unconnected-(EXPANSION-Pad7)") (class "Default")
      (node (ref "EXPANSION") (pin "7") (pinfunction "7_7") (pintype "passive"))
    )
    (net (code "68") (name "unconnected-(U3-DEN(G)-Pad10)") (class "Default")
      (node (ref "U3") (pin "10") (pinfunction "DEN(G)_10") (pintype "bidirectional"))
    )
    (net (code "69") (name "unconnected-(U3-DRDY(G)-Pad12)") (class "Default")
      (node (ref "U3") (pin "12") (pinfunction "DRDY(G)_12") (pintype "bidirectional"))
    )
    (net (code "70") (name "unconnected-(U3-INT(G)-Pad11)") (class "Default")
      (node (ref "U3") (pin "11") (pinfunction "INT(G)_11") (pintype "bidirectional"))
    )
    (net (code "71") (name "unconnected-(U3-INT1(XM)-Pad13)") (class "Default")
      (node (ref "U3") (pin "13") (pinfunction "INT1(XM)_13") (pintype "bidirectional"))
    )
    (net (code "72") (name "unconnected-(U3-INT2(XM)-Pad14)") (class "Default")
      (node (ref "U3") (pin "14") (pinfunction "INT2(XM)_14") (pintype "bidirectional"))
    )
    (net (code "73") (name "unconnected-(U4A-PB1-Pad27)") (class "Default")
      (node (ref "U4") (pin "27") (pinfunction "PB1_27") (pintype "bidirectional"))
    )
    (net (code "74") (name "unconnected-(U4A-PB10-Pad29)") (class "Default")
      (node (ref "U4") (pin "29") (pinfunction "PB10_29") (pintype "bidirectional"))
    )
    (net (code "75") (name "unconnected-(U4A-PC1-Pad9)") (class "Default")
      (node (ref "U4") (pin "9") (pinfunction "PC1_9") (pintype "bidirectional"))
    )
    (net (code "76") (name "unconnected-(U4A-PC2-Pad10)") (class "Default")
      (node (ref "U4") (pin "10") (pinfunction "PC2_10") (pintype "bidirectional"))
    )
    (net (code "77") (name "unconnected-(U4A-PC3-Pad11)") (class "Default")
      (node (ref "U4") (pin "11") (pinfunction "PC3_11") (pintype "bidirectional"))
    )
    (net (code "78") (name "unconnected-(U4A-PC4-Pad24)") (class "Default")
      (node (ref "U4") (pin "24") (pinfunction "PC4_24") (pintype "bidirectional"))
    )
    (net (code "79") (name "unconnected-(U4A-PC5-Pad25)") (class "Default")
      (node (ref "U4") (pin "25") (pinfunction "PC5_25") (pintype "bidirectional"))
    )
    (net (code "80") (name "unconnected-(U4A-PC13-Pad2)") (class "Default")
      (node (ref "U4") (pin "2") (pinfunction "PC13_2") (pintype "bidirectional"))
    )
    (net (code "81") (name "unconnected-(U4A-PC14-OSC32_IN-Pad3)") (class "Default")
      (node (ref "U4") (pin "3") (pinfunction "PC14-OSC32_IN_3") (pintype "bidirectional"))
    )
    (net (code "82") (name "unconnected-(U4A-PC15-OSC32_OUT-Pad4)") (class "Default")
      (node (ref "U4") (pin "4") (pinfunction "PC15-OSC32_OUT_4") (pintype "bidirectional"))
    )
    (net (code "83") (name "unconnected-(U4A-PF4-Pad18)") (class "Default")
      (node (ref "U4") (pin "18") (pinfunction "PF4_18") (pintype "bidirectional"))
    )
    (net (code "84") (name "unconnected-(U4B-PA15-Pad50)") (class "Default")
      (node (ref "U4") (pin "50") (pinfunction "PA15_50") (pintype "bidirectional"))
    )
    (net (code "85") (name "unconnected-(U4B-PB3-Pad55)") (class "Default")
      (node (ref "U4") (pin "55") (pinfunction "PB3_55") (pintype "bidirectional"))
    )
    (net (code "86") (name "unconnected-(U4B-PC8-Pad39)") (class "Default")
      (node (ref "U4") (pin "39") (pinfunction "PC8_39") (pintype "bidirectional"))
    )
    (net (code "87") (name "unconnected-(U4B-PC9-Pad40)") (class "Default")
      (node (ref "U4") (pin "40") (pinfunction "PC9_40") (pintype "bidirectional"))
    )
    (net (code "88") (name "unconnected-(USER-Pad4)") (class "Default")
      (node (ref "USER") (pin "4") (pinfunction "4_4") (pintype "passive"))
    )
    (net (code "89") (name "unconnected-(X1-Pad4)") (class "Default")
      (node (ref "X1") (pin "4") (pinfunction "4_4") (pintype "passive"))
    )
  )
)
